# Arduino_Shield_1_19_19_REV0.net
KiCad netlist of a schematic drawn in EAGLE
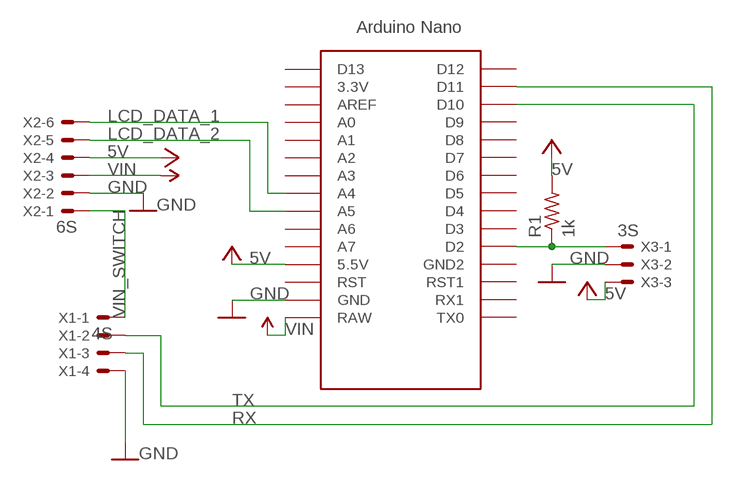
[diagram p0: schematic, sheet 1]

(export (version "E")
  (design (tool "Eeschema 10.0.6"))
  (components
    (comp (ref "R1")
      (value "1k")
      (footprint "eagle-import:R0805")
      (libsource (lib "eagle-import") (part "R-US_R0805"))
    )
    (comp (ref "U$1")
      (value "NANO")
      (footprint "eagle-import:NANO")
      (libsource (lib "eagle-import") (part "NANO"))
    )
    (comp (ref "X1")
      (value "4S")
      (footprint "eagle-import:JST-XH-04-PACKAGE-ROUND-PAD")
      (libsource (lib "eagle-import") (part "JST-XH-04-PIN-ROUND-PAD"))
    )
    (comp (ref "X2")
      (value "6S")
      (footprint "eagle-import:JST-XH-06-PACKAGE-ROUND-PAD")
      (libsource (lib "eagle-import") (part "JST-XH-06-PIN-ROUND-PAD"))
    )
    (comp (ref "X3")
      (value "3S")
      (footprint "eagle-import:JST-XH-03-PACKAGE-ROUND-PAD")
      (libsource (lib "eagle-import") (part "JST-XH-03-PIN-ROUND-PAD"))
    )
  )
  (nets
    (net (code "1") (name "/LCD_DATA_1") (class "Default")
      (node (ref "U$1") (pin "A4") (pinfunction "A4_A4") (pintype "bidirectional"))
      (node (ref "X2") (pin "6") (pinfunction "S_6") (pintype "passive"))
    )
    (net (code "2") (name "/LCD_DATA_2") (class "Default")
      (node (ref "U$1") (pin "A5") (pinfunction "A5_A5") (pintype "bidirectional"))
      (node (ref "X2") (pin "5") (pinfunction "S_5") (pintype "passive"))
    )
    (net (code "3") (name "/RX") (class "Default")
      (node (ref "U$1") (pin "D11") (pinfunction "D11_D11") (pintype "bidirectional"))
      (node (ref "X1") (pin "3") (pinfunction "S_3") (pintype "passive"))
    )
    (net (code "4") (name "/TX") (class "Default")
      (node (ref "U$1") (pin "D10") (pinfunction "D10_D10") (pintype "bidirectional"))
      (node (ref "X1") (pin "2") (pinfunction "S_2") (pintype "passive"))
    )
    (net (code "5") (name "/VIN_SWITCH") (class "Default")
      (node (ref "X1") (pin "1") (pinfunction "S_1") (pintype "passive"))
      (node (ref "X2") (pin "1") (pinfunction "S_1") (pintype "passive"))
    )
    (net (code "6") (name "GND") (class "Default")
      (node (ref "U$1") (pin "GND") (pinfunction "GND_GND") (pintype "bidirectional"))
      (node (ref "X1") (pin "4") (pinfunction "S_4") (pintype "passive"))
      (node (ref "X2") (pin "2") (pinfunction "S_2") (pintype "passive"))
      (node (ref "X3") (pin "2") (pinfunction "S_2") (pintype "passive"))
    )
    (net (code "7") (name "Net-(X3A-S)") (class "Default")
      (node (ref "R1") (pin "1") (pinfunction "1_1") (pintype "passive"))
      (node (ref "U$1") (pin "D2") (pinfunction "D2_D2") (pintype "bidirectional"))
      (node (ref "X3") (pin "1") (pinfunction "S_1") (pintype "passive"))
    )
    (net (code "8") (name "VCC") (class "Default")
      (node (ref "R1") (pin "2") (pinfunction "2_2") (pintype "passive"))
      (node (ref "U$1") (pin "5V") (pinfunction "5.5V_5V") (pintype "bidirectional"))
      (node (ref "X2") (pin "4") (pinfunction "S_4") (pintype "passive"))
      (node (ref "X3") (pin "3") (pinfunction "S_3") (pintype "passive"))
    )
    (net (code "9") (name "VIN") (class "Default")
      (node (ref "U$1") (pin "RAW") (pinfunction "RAW_RAW") (pintype "bidirectional"))
      (node (ref "X2") (pin "3") (pinfunction "S_3") (pintype "passive"))
    )
    (net (code "10") (name "unconnected-(U$1-GND2-PadGND1)") (class "Default")
      (node (ref "U$1") (pin "GND1") (pinfunction "GND2_GND1") (pintype "bidirectional"))
    )
    (net (code "11") (name "unconnected-(U$1-Pad3.3V)") (class "Default")
      (node (ref "U$1") (pin "3.3V") (pinfunction "3.3V_3.3V") (pintype "bidirectional"))
    )
    (net (code "12") (name "unconnected-(U$1-PadA0)") (class "Default")
      (node (ref "U$1") (pin "A0") (pinfunction "A0_A0") (pintype "bidirectional"))
    )
    (net (code "13") (name "unconnected-(U$1-PadA1)") (class "Default")
      (node (ref "U$1") (pin "A1") (pinfunction "A1_A1") (pintype "bidirectional"))
    )
    (net (code "14") (name "unconnected-(U$1-PadA2)") (class "Default")
      (node (ref "U$1") (pin "A2") (pinfunction "A2_A2") (pintype "bidirectional"))
    )
    (net (code "15") (name "unconnected-(U$1-PadA3)") (class "Default")
      (node (ref "U$1") (pin "A3") (pinfunction "A3_A3") (pintype "bidirectional"))
    )
    (net (code "16") (name "unconnected-(U$1-PadA6)") (class "Default")
      (node (ref "U$1") (pin "A6") (pinfunction "A6_A6") (pintype "bidirectional"))
    )
    (net (code "17") (name "unconnected-(U$1-PadA7)") (class "Default")
      (node (ref "U$1") (pin "A7") (pinfunction "A7_A7") (pintype "bidirectional"))
    )
    (net (code "18") (name "unconnected-(U$1-PadAREF)") (class "Default")
      (node (ref "U$1") (pin "AREF") (pinfunction "AREF_AREF") (pintype "bidirectional"))
    )
    (net (code "19") (name "unconnected-(U$1-PadD3)") (class "Default")
      (node (ref "U$1") (pin "D3") (pinfunction "D3_D3") (pintype "bidirectional"))
    )
    (net (code "20") (name "unconnected-(U$1-PadD4)") (class "Default")
      (node (ref "U$1") (pin "D4") (pinfunction "D4_D4") (pintype "bidirectional"))
    )
    (net (code "21") (name "unconnected-(U$1-PadD5)") (class "Default")
      (node (ref "U$1") (pin "D5") (pinfunction "D5_D5") (pintype "bidirectional"))
    )
    (net (code "22") (name "unconnected-(U$1-PadD6)") (class "Default")
      (node (ref "U$1") (pin "D6") (pinfunction "D6_D6") (pintype "bidirectional"))
    )
    (net (code "23") (name "unconnected-(U$1-PadD7)") (class "Default")
      (node (ref "U$1") (pin "D7") (pinfunction "D7_D7") (pintype "bidirectional"))
    )
    (net (code "24") (name "unconnected-(U$1-PadD8)") (class "Default")
      (node (ref "U$1") (pin "D8") (pinfunction "D8_D8") (pintype "bidirectional"))
    )
    (net (code "25") (name "unconnected-(U$1-PadD9)") (class "Default")
      (node (ref "U$1") (pin "D9") (pinfunction "D9_D9") (pintype "bidirectional"))
    )
    (net (code "26") (name "unconnected-(U$1-PadD12)") (class "Default")
      (node (ref "U$1") (pin "D12") (pinfunction "D12_D12") (pintype "bidirectional"))
    )
    (net (code "27") (name "unconnected-(U$1-PadD13)") (class "Default")
      (node (ref "U$1") (pin "D13") (pinfunction "D13_D13") (pintype "bidirectional"))
    )
    (net (code "28") (name "unconnected-(U$1-PadICSP1)") (class "Default")
      (node (ref "U$1") (pin "ICSP1") (pinfunction "ICSP1_ICSP1") (pintype "bidirectional"))
    )
    (net (code "29") (name "unconnected-(U$1-PadICSP2)") (class "Default")
      (node (ref "U$1") (pin "ICSP2") (pinfunction "ICSP2_ICSP2") (pintype "bidirectional"))
    )
    (net (code "30") (name "unconnected-(U$1-PadICSP3)") (class "Default")
      (node (ref "U$1") (pin "ICSP3") (pinfunction "ICSP3_ICSP3") (pintype "bidirectional"))
    )
    (net (code "31") (name "unconnected-(U$1-PadICSP4)") (class "Default")
      (node (ref "U$1") (pin "ICSP4") (pinfunction "ICSP4_ICSP4") (pintype "bidirectional"))
    )
    (net (code "32") (name "unconnected-(U$1-PadICSP5)") (class "Default")
      (node (ref "U$1") (pin "ICSP5") (pinfunction "ICSP5_ICSP5") (pintype "bidirectional"))
    )
    (net (code "33") (name "unconnected-(U$1-PadICSP6)") (class "Default")
      (node (ref "U$1") (pin "ICSP6") (pinfunction "ICSP6_ICSP6") (pintype "bidirectional"))
    )
    (net (code "34") (name "unconnected-(U$1-PadRST)") (class "Default")
      (node (ref "U$1") (pin "RST") (pinfunction "RST_RST") (pintype "bidirectional"))
    )
    (net (code "35") (name "unconnected-(U$1-PadRST1)") (class "Default")
      (node (ref "U$1") (pin "RST1") (pinfunction "RST1_RST1") (pintype "bidirectional"))
    )
    (net (code "36") (name "unconnected-(U$1-PadRX1)") (class "Default")
      (node (ref "U$1") (pin "RX1") (pinfunction "RX1_RX1") (pintype "bidirectional"))
    )
    (net (code "37") (name "unconnected-(U$1-PadTX0)") (class "Default")
      (node (ref "U$1") (pin "TX0") (pinfunction "TX0_TX0") (pintype "bidirectional"))
    )
  )
)
